# MC10EP51.net
KiCad netlist of a schematic drawn in Altium Designer
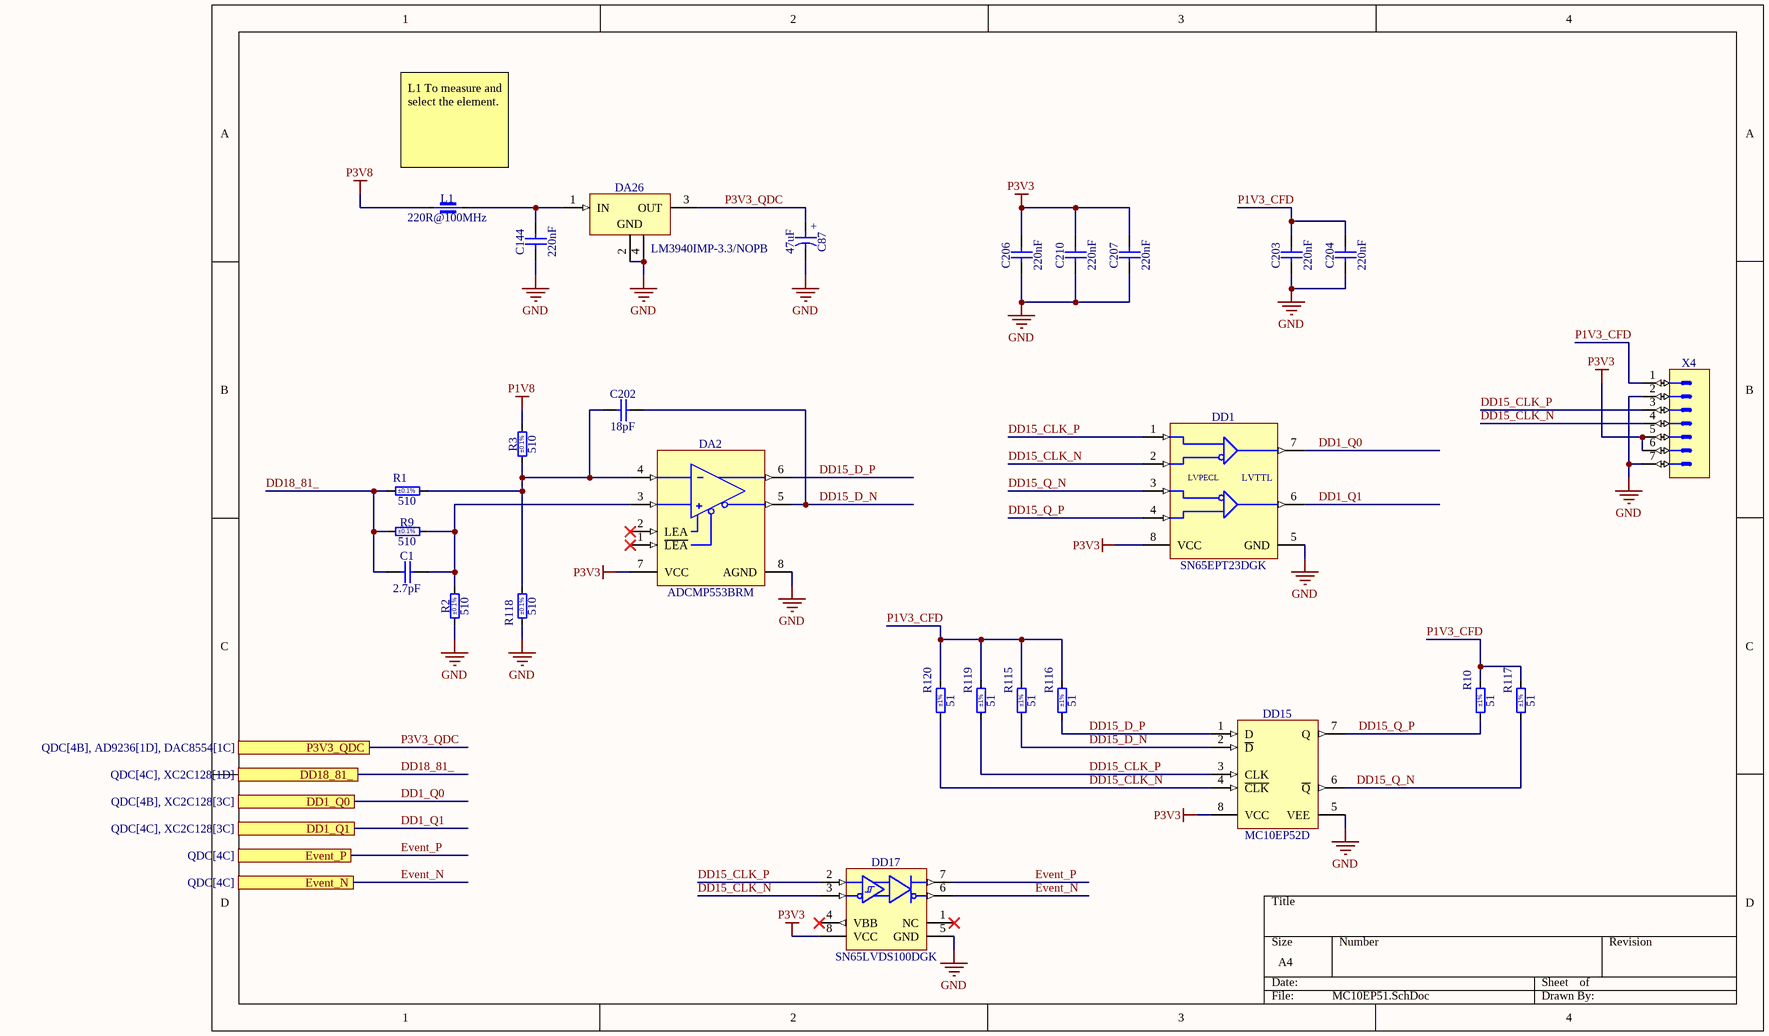
[diagram p0: MC10EP51.SchDoc]

(export (version "E")
  (design (tool "Eeschema 10.0.6"))
  (components
    (comp (ref "C1")
      (value "2.7pF")
      (footprint "CAPC2012X135N")
      (description "Non-polarised capacitor")
      (fields
        (field (name "PART NUMBER") "CC0805_2.7PF_250V_0.05PF_NP0")
        (field (name "VOLTAGE") "50V")
        (field (name "AUTHOR") "CERN DEM HF")
      )
      (libsource (lib "Capacitors") (part "Capacitor - non polarized"))
    )
    (comp (ref "C87")
      (value "47uF")
      (footprint "CAPAE530X610N")
      (description "Polarised capacitor")
      (fields
        (field (name "PART NUMBER") "CAE530-610_47UF_16V_20%")
        (field (name "VOLTAGE") "16V")
        (field (name "AUTHOR") "CERN DEM HF")
      )
      (libsource (lib "Capacitors") (part "Capacitor - polarized"))
    )
    (comp (ref "C144")
      (value "220nF")
      (footprint "CAPC2012X135N")
      (description "Non-polarised capacitor")
      (fields
        (field (name "PART NUMBER") "CC0805_220NF_50V_10%_X7R")
        (field (name "VOLTAGE") "50V")
        (field (name "AUTHOR") "CERN DEM JLC")
      )
      (libsource (lib "Capacitors") (part "Capacitor - non polarized"))
    )
    (comp (ref "C202")
      (value "18pF")
      (footprint "CAPC2012X88N")
      (description "Non-polarised capacitor")
      (fields
        (field (name "PART NUMBER") "CC0805_18PF_50V_1%_C0G")
        (field (name "VOLTAGE") "50V")
        (field (name "AUTHOR") "CERN DEM JLC")
      )
      (libsource (lib "Capacitors") (part "Capacitor - non polarized"))
    )
    (comp (ref "C203")
      (value "220nF")
      (footprint "CAPC2012X135N")
      (description "Non-polarised capacitor")
      (fields
        (field (name "PART NUMBER") "CC0805_220NF_50V_10%_X7R")
        (field (name "VOLTAGE") "50V")
        (field (name "AUTHOR") "CERN DEM JLC")
      )
      (libsource (lib "Capacitors") (part "Capacitor - non polarized"))
    )
    (comp (ref "C204")
      (value "220nF")
      (footprint "CAPC2012X135N")
      (description "Non-polarised capacitor")
      (fields
        (field (name "PART NUMBER") "CC0805_220NF_50V_10%_X7R")
        (field (name "VOLTAGE") "50V")
        (field (name "AUTHOR") "CERN DEM JLC")
      )
      (libsource (lib "Capacitors") (part "Capacitor - non polarized"))
    )
    (comp (ref "C206")
      (value "220nF")
      (footprint "CAPC2012X135N")
      (description "Non-polarised capacitor")
      (fields
        (field (name "PART NUMBER") "CC0805_220NF_50V_10%_X7R")
        (field (name "VOLTAGE") "50V")
        (field (name "AUTHOR") "CERN DEM JLC")
      )
      (libsource (lib "Capacitors") (part "Capacitor - non polarized"))
    )
    (comp (ref "C207")
      (value "220nF")
      (footprint "CAPC2012X135N")
      (description "Non-polarised capacitor")
      (fields
        (field (name "PART NUMBER") "CC0805_220NF_50V_10%_X7R")
        (field (name "VOLTAGE") "50V")
        (field (name "AUTHOR") "CERN DEM JLC")
      )
      (libsource (lib "Capacitors") (part "Capacitor - non polarized"))
    )
    (comp (ref "C210")
      (value "220nF")
      (footprint "CAPC2012X135N")
      (description "Non-polarised capacitor")
      (fields
        (field (name "PART NUMBER") "CC0805_220NF_50V_10%_X7R")
        (field (name "VOLTAGE") "50V")
        (field (name "AUTHOR") "CERN DEM JLC")
      )
      (libsource (lib "Capacitors") (part "Capacitor - non polarized"))
    )
    (comp (ref "DA2")
      (value "ADCMP553BRM")
      (footprint "SOP65P490X110-8N")
      (description "Single-Supply, High Speed PECL/LVPECL Comparators")
      (fields (field (name "MANUFACTURER") "ANALOG DEVICES") (field (name "AUTHOR") "CERN DEM HF"))
      (libsource (lib "ICs And Semiconductors") (part "ADCMP553BRM"))
    )
    (comp (ref "DA26")
      (value "LM3940IMP-3.3/NOPB")
      (footprint "SOT230P700X180-4N")
      (description "3-Terminal Regulator 1=IN 2=GND 3=OUT 4=GND")
      (fields
        (field (name "MANUFACTURER") "TEXAS INSTRUMENTS")
        (field (name "MANUFACTURER PART NUMBER") "LM3940IMP-3.3")
        (field (name "AUTHOR") "CERN DEM JLC")
      )
      (libsource (lib "ICs And Semiconductors") (part "REG3+1 1IN-2GND-3OUT+4GND"))
    )
    (comp (ref "DD1")
      (value "SN65EPT23DGK")
      (footprint "SOP65P490X110-8N")
      (description "5V PECL to TTL Translator")
      (fields (field (name "MANUFACTURER") "TEXAS INSTRUMENTS") (field (name "AUTHOR") "CERN DEM HF"))
      (libsource (lib "ICs And Semiconductors") (part "SN65EPT23"))
    )
    (comp (ref "DD15")
      (value "MC10EP52D")
      (footprint "SOIC127P600X175-8N")
      (description "3.3V/5V ECL Differential Data and Clock D Flip-Flop")
      (fields (field (name "MANUFACTURER") "ON SEMICONDUCTOR") (field (name "AUTHOR") "CERN DEM HF"))
      (libsource (lib "ICs And Semiconductors") (part "100EP52"))
    )
    (comp (ref "DD17")
      (value "SN65LVDS100DGK")
      (footprint "SOP65P490X110-8N")
      (description "Differential LVDS Translator/Repeater")
      (fields (field (name "MANUFACTURER") "TEXAS INSTRUMENTS") (field (name "AUTHOR") "CERN DEM JLC"))
      (libsource (lib "ICs And Semiconductors") (part "SN65LVDS100"))
    )
    (comp (ref "L1")
      (value "220R@100MHz")
      (footprint "INDC2012X105N")
      (fields
        (field (name "PART NUMBER") "IND0805_TDK_MPZ2012S221A")
        (field (name "POWER") "3A")
        (field (name "TOLERANCE") "±25%")
        (field (name "AUTHOR") "CERN DEM HF")
      )
      (libsource (lib "Inductors & Transformers") (part "Ferrite Bead"))
    )
    (comp (ref "R1")
      (value "510")
      (footprint "RESC2012X60N")
      (description "Resistor - 0.1%")
      (fields
        (field (name "TOLERANCE") "±0.1%")
        (field (name "PART NUMBER") "R0805_510R_0.1%_0.125W_10PPM")
        (field (name "POWER") "0.125W")
        (field (name "AUTHOR") "CERN DEM HF")
      )
      (libsource (lib "Resistors") (part "Resistor - 0.1%"))
    )
    (comp (ref "R2")
      (value "510")
      (footprint "RESC2012X60N")
      (description "Resistor - 0.1%")
      (fields
        (field (name "TOLERANCE") "±0.1%")
        (field (name "PART NUMBER") "R0805_510R_0.1%_0.125W_10PPM")
        (field (name "POWER") "0.125W")
        (field (name "AUTHOR") "CERN DEM HF")
      )
      (libsource (lib "Resistors") (part "Resistor - 0.1%"))
    )
    (comp (ref "R3")
      (value "510")
      (footprint "RESC2012X60N")
      (description "Resistor - 0.1%")
      (fields
        (field (name "TOLERANCE") "±0.1%")
        (field (name "PART NUMBER") "R0805_510R_0.1%_0.125W_10PPM")
        (field (name "POWER") "0.125W")
        (field (name "AUTHOR") "CERN DEM HF")
      )
      (libsource (lib "Resistors") (part "Resistor - 0.1%"))
    )
    (comp (ref "R9")
      (value "510")
      (footprint "RESC2012X60N")
      (description "Resistor - 0.1%")
      (fields
        (field (name "TOLERANCE") "±0.1%")
        (field (name "PART NUMBER") "R0805_510R_0.1%_0.125W_10PPM")
        (field (name "POWER") "0.125W")
        (field (name "AUTHOR") "CERN DEM HF")
      )
      (libsource (lib "Resistors") (part "Resistor - 0.1%"))
    )
    (comp (ref "R10")
      (value "51")
      (footprint "RESC2012X60N")
      (description "Resistor - 1%")
      (fields
        (field (name "TOLERANCE") "±1%")
        (field (name "PART NUMBER") "R0805_51R_1%_0.125W_100PPM")
        (field (name "POWER") "0.125W")
        (field (name "AUTHOR") "CERN DEM JLC")
      )
      (libsource (lib "Resistors") (part "Resistor - 1%"))
    )
    (comp (ref "R115")
      (value "51")
      (footprint "RESC2012X60N")
      (description "Resistor - 1%")
      (fields
        (field (name "TOLERANCE") "±1%")
        (field (name "PART NUMBER") "R0805_51R_1%_0.125W_100PPM")
        (field (name "POWER") "0.125W")
        (field (name "AUTHOR") "CERN DEM JLC")
      )
      (libsource (lib "Resistors") (part "Resistor - 1%"))
    )
    (comp (ref "R116")
      (value "51")
      (footprint "RESC2012X60N")
      (description "Resistor - 1%")
      (fields
        (field (name "TOLERANCE") "±1%")
        (field (name "PART NUMBER") "R0805_51R_1%_0.125W_100PPM")
        (field (name "POWER") "0.125W")
        (field (name "AUTHOR") "CERN DEM JLC")
      )
      (libsource (lib "Resistors") (part "Resistor - 1%"))
    )
    (comp (ref "R117")
      (value "51")
      (footprint "RESC2012X60N")
      (description "Resistor - 1%")
      (fields
        (field (name "TOLERANCE") "±1%")
        (field (name "PART NUMBER") "R0805_51R_1%_0.125W_100PPM")
        (field (name "POWER") "0.125W")
        (field (name "AUTHOR") "CERN DEM JLC")
      )
      (libsource (lib "Resistors") (part "Resistor - 1%"))
    )
    (comp (ref "R118")
      (value "510")
      (footprint "RESC2012X60N")
      (description "Resistor - 0.1%")
      (fields
        (field (name "TOLERANCE") "±0.1%")
        (field (name "PART NUMBER") "R0805_510R_0.1%_0.125W_10PPM")
        (field (name "POWER") "0.125W")
        (field (name "AUTHOR") "CERN DEM HF")
      )
      (libsource (lib "Resistors") (part "Resistor - 0.1%"))
    )
    (comp (ref "R119")
      (value "51")
      (footprint "RESC2012X60N")
      (description "Resistor - 1%")
      (fields
        (field (name "TOLERANCE") "±1%")
        (field (name "PART NUMBER") "R0805_51R_1%_0.125W_100PPM")
        (field (name "POWER") "0.125W")
        (field (name "AUTHOR") "CERN DEM JLC")
      )
      (libsource (lib "Resistors") (part "Resistor - 1%"))
    )
    (comp (ref "R120")
      (value "51")
      (footprint "RESC2012X60N")
      (description "Resistor - 1%")
      (fields
        (field (name "TOLERANCE") "±1%")
        (field (name "PART NUMBER") "R0805_51R_1%_0.125W_100PPM")
        (field (name "POWER") "0.125W")
        (field (name "AUTHOR") "CERN DEM JLC")
      )
      (libsource (lib "Resistors") (part "Resistor - 1%"))
    )
    (comp (ref "X4")
      (value "Header 7")
      (footprint "SAMTEC_DW-07-09-L-S-470")
      (description "Connector 7 Male")
      (fields
        (field (name "PART NUMBER") "SAMTEC_DW-07-09-L-S-470")
        (field (name "MANUFACTURER") "SAMTEC")
        (field (name "AUTHOR") "CERN DEM HF")
      )
      (libsource (lib "Connectors") (part "Connector 7 Male"))
    )
  )
  (nets
    (net (code "1") (name "/DD1_Q0") (class "Default")
      (node (ref "DD1") (pin "7") (pinfunction "Q0_7") (pintype "output"))
    )
    (net (code "2") (name "/DD1_Q1") (class "Default")
      (node (ref "DD1") (pin "6") (pinfunction "Q1_6") (pintype "output"))
    )
    (net (code "3") (name "/DD15_CLK_N") (class "Default")
      (node (ref "DD1") (pin "2") (pinfunction "~{D0}_2") (pintype "input"))
      (node (ref "DD15") (pin "4") (pinfunction "~{CLK}_4") (pintype "input"))
      (node (ref "DD17") (pin "3") (pinfunction "B_3") (pintype "input"))
      (node (ref "R120") (pin "1") (pinfunction "1_1") (pintype "passive"))
      (node (ref "X4") (pin "4") (pinfunction "4_4") (pintype "bidirectional"))
    )
    (net (code "4") (name "/DD15_CLK_P") (class "Default")
      (node (ref "DD1") (pin "1") (pinfunction "D0_1") (pintype "input"))
      (node (ref "DD15") (pin "3") (pinfunction "CLK_3") (pintype "input"))
      (node (ref "DD17") (pin "2") (pinfunction "A_2") (pintype "input"))
      (node (ref "R119") (pin "1") (pinfunction "1_1") (pintype "passive"))
      (node (ref "X4") (pin "3") (pinfunction "3_3") (pintype "bidirectional"))
    )
    (net (code "5") (name "/DD15_D_N") (class "Default")
      (node (ref "C202") (pin "2") (pinfunction "2_2") (pintype "passive"))
      (node (ref "DA2") (pin "5") (pinfunction "~{QA}_5") (pintype "output"))
      (node (ref "DD15") (pin "2") (pinfunction "~{D}_2") (pintype "input"))
      (node (ref "R115") (pin "1") (pinfunction "1_1") (pintype "passive"))
    )
    (net (code "6") (name "/DD15_D_P") (class "Default")
      (node (ref "DA2") (pin "6") (pinfunction "QA_6") (pintype "output"))
      (node (ref "DD15") (pin "1") (pinfunction "D_1") (pintype "input"))
      (node (ref "R116") (pin "1") (pinfunction "1_1") (pintype "passive"))
    )
    (net (code "7") (name "/DD15_Q_N") (class "Default")
      (node (ref "DD1") (pin "3") (pinfunction "~{D1}_3") (pintype "input"))
      (node (ref "DD15") (pin "6") (pinfunction "~{Q}_6") (pintype "output"))
      (node (ref "R117") (pin "1") (pinfunction "1_1") (pintype "passive"))
    )
    (net (code "8") (name "/DD15_Q_P") (class "Default")
      (node (ref "DD1") (pin "4") (pinfunction "D1_4") (pintype "input"))
      (node (ref "DD15") (pin "7") (pinfunction "Q_7") (pintype "output"))
      (node (ref "R10") (pin "1") (pinfunction "1_1") (pintype "passive"))
    )
    (net (code "9") (name "/DD18_81_") (class "Default")
      (node (ref "C1") (pin "1") (pinfunction "1_1") (pintype "passive"))
      (node (ref "R1") (pin "1") (pinfunction "1_1") (pintype "passive"))
      (node (ref "R9") (pin "1") (pinfunction "1_1") (pintype "passive"))
    )
    (net (code "10") (name "/Event_N") (class "Default")
      (node (ref "DD17") (pin "6") (pinfunction "Z_6") (pintype "output"))
    )
    (net (code "11") (name "/Event_P") (class "Default")
      (node (ref "DD17") (pin "7") (pinfunction "Y_7") (pintype "output"))
    )
    (net (code "12") (name "/P1V3_CFD") (class "Default")
      (node (ref "C203") (pin "2") (pinfunction "2_2") (pintype "passive"))
      (node (ref "C204") (pin "2") (pinfunction "2_2") (pintype "passive"))
      (node (ref "R10") (pin "2") (pinfunction "2_2") (pintype "passive"))
      (node (ref "R115") (pin "2") (pinfunction "2_2") (pintype "passive"))
      (node (ref "R116") (pin "2") (pinfunction "2_2") (pintype "passive"))
      (node (ref "R117") (pin "2") (pinfunction "2_2") (pintype "passive"))
      (node (ref "R119") (pin "2") (pinfunction "2_2") (pintype "passive"))
      (node (ref "R120") (pin "2") (pinfunction "2_2") (pintype "passive"))
      (node (ref "X4") (pin "1") (pinfunction "1_1") (pintype "bidirectional"))
    )
    (net (code "13") (name "/P3V3_QDC") (class "Default")
      (node (ref "C87") (pin "1") (pinfunction "1_1") (pintype "passive"))
      (node (ref "DA26") (pin "3") (pinfunction "OUT_3") (pintype "power_in"))
    )
    (net (code "14") (name "GND") (class "Default")
      (node (ref "C144") (pin "1") (pinfunction "1_1") (pintype "passive"))
      (node (ref "C203") (pin "1") (pinfunction "1_1") (pintype "passive"))
      (node (ref "C204") (pin "1") (pinfunction "1_1") (pintype "passive"))
      (node (ref "C206") (pin "1") (pinfunction "1_1") (pintype "passive"))
      (node (ref "C207") (pin "1") (pinfunction "1_1") (pintype "passive"))
      (node (ref "C210") (pin "1") (pinfunction "1_1") (pintype "passive"))
      (node (ref "C87") (pin "2") (pinfunction "2_2") (pintype "passive"))
      (node (ref "DA2") (pin "8") (pinfunction "AGND_8") (pintype "power_in"))
      (node (ref "DA26") (pin "2") (pinfunction "GND_2") (pintype "power_in"))
      (node (ref "DA26") (pin "4") (pinfunction "GND_4") (pintype "power_in"))
      (node (ref "DD1") (pin "5") (pinfunction "GND_5") (pintype "power_in"))
      (node (ref "DD15") (pin "5") (pinfunction "VEE_5") (pintype "power_in"))
      (node (ref "DD17") (pin "5") (pinfunction "GND_5") (pintype "power_in"))
      (node (ref "R118") (pin "1") (pinfunction "1_1") (pintype "passive"))
      (node (ref "R2") (pin "1") (pinfunction "1_1") (pintype "passive"))
      (node (ref "X4") (pin "2") (pinfunction "2_2") (pintype "bidirectional"))
      (node (ref "X4") (pin "7") (pinfunction "7_7") (pintype "bidirectional"))
    )
    (net (code "15") (name "Net-(DA2-+INA)") (class "Default")
      (node (ref "C1") (pin "2") (pinfunction "2_2") (pintype "passive"))
      (node (ref "DA2") (pin "3") (pinfunction "+INA_3") (pintype "input"))
      (node (ref "R2") (pin "2") (pinfunction "2_2") (pintype "passive"))
      (node (ref "R9") (pin "2") (pinfunction "2_2") (pintype "passive"))
    )
    (net (code "16") (name "Net-(DA2--INA)") (class "Default")
      (node (ref "C202") (pin "1") (pinfunction "1_1") (pintype "passive"))
      (node (ref "DA2") (pin "4") (pinfunction "-INA_4") (pintype "input"))
      (node (ref "R1") (pin "2") (pinfunction "2_2") (pintype "passive"))
      (node (ref "R118") (pin "2") (pinfunction "2_2") (pintype "passive"))
      (node (ref "R3") (pin "1") (pinfunction "1_1") (pintype "passive"))
    )
    (net (code "17") (name "Net-(DA26-IN)") (class "Default")
      (node (ref "C144") (pin "2") (pinfunction "2_2") (pintype "passive"))
      (node (ref "DA26") (pin "1") (pinfunction "IN_1") (pintype "input"))
      (node (ref "L1") (pin "2") (pinfunction "2_2") (pintype "passive"))
    )
    (net (code "18") (name "P1V8") (class "Default")
      (node (ref "R3") (pin "2") (pinfunction "2_2") (pintype "passive"))
    )
    (net (code "19") (name "P3V3") (class "Default")
      (node (ref "C206") (pin "2") (pinfunction "2_2") (pintype "passive"))
      (node (ref "C207") (pin "2") (pinfunction "2_2") (pintype "passive"))
      (node (ref "C210") (pin "2") (pinfunction "2_2") (pintype "passive"))
      (node (ref "DA2") (pin "7") (pinfunction "VCC_7") (pintype "power_in"))
      (node (ref "DD1") (pin "8") (pinfunction "VCC_8") (pintype "power_in"))
      (node (ref "DD15") (pin "8") (pinfunction "VCC_8") (pintype "power_in"))
      (node (ref "DD17") (pin "8") (pinfunction "VCC_8") (pintype "power_in"))
      (node (ref "X4") (pin "5") (pinfunction "5_5") (pintype "bidirectional"))
      (node (ref "X4") (pin "6") (pinfunction "6_6") (pintype "bidirectional"))
    )
    (net (code "20") (name "P3V8") (class "Default")
      (node (ref "L1") (pin "1") (pinfunction "1_1") (pintype "passive"))
    )
    (net (code "21") (name "unconnected-(DA2-LEA-Pad2)") (class "Default")
      (node (ref "DA2") (pin "2") (pinfunction "LEA_2") (pintype "input+no_connect"))
    )
    (net (code "22") (name "unconnected-(DA2-~{LEA}-Pad1)") (class "Default")
      (node (ref "DA2") (pin "1") (pinfunction "~{LEA}_1") (pintype "input+no_connect"))
    )
    (net (code "23") (name "unconnected-(DD17-NC-Pad1)") (class "Default")
      (node (ref "DD17") (pin "1") (pinfunction "NC_1") (pintype "passive+no_connect"))
    )
    (net (code "24") (name "unconnected-(DD17-VBB-Pad4)") (class "Default")
      (node (ref "DD17") (pin "4") (pinfunction "VBB_4") (pintype "output+no_connect"))
    )
  )
)
